# 03_BGT24LTR11.net
KiCad netlist of a schematic drawn in Altium Designer
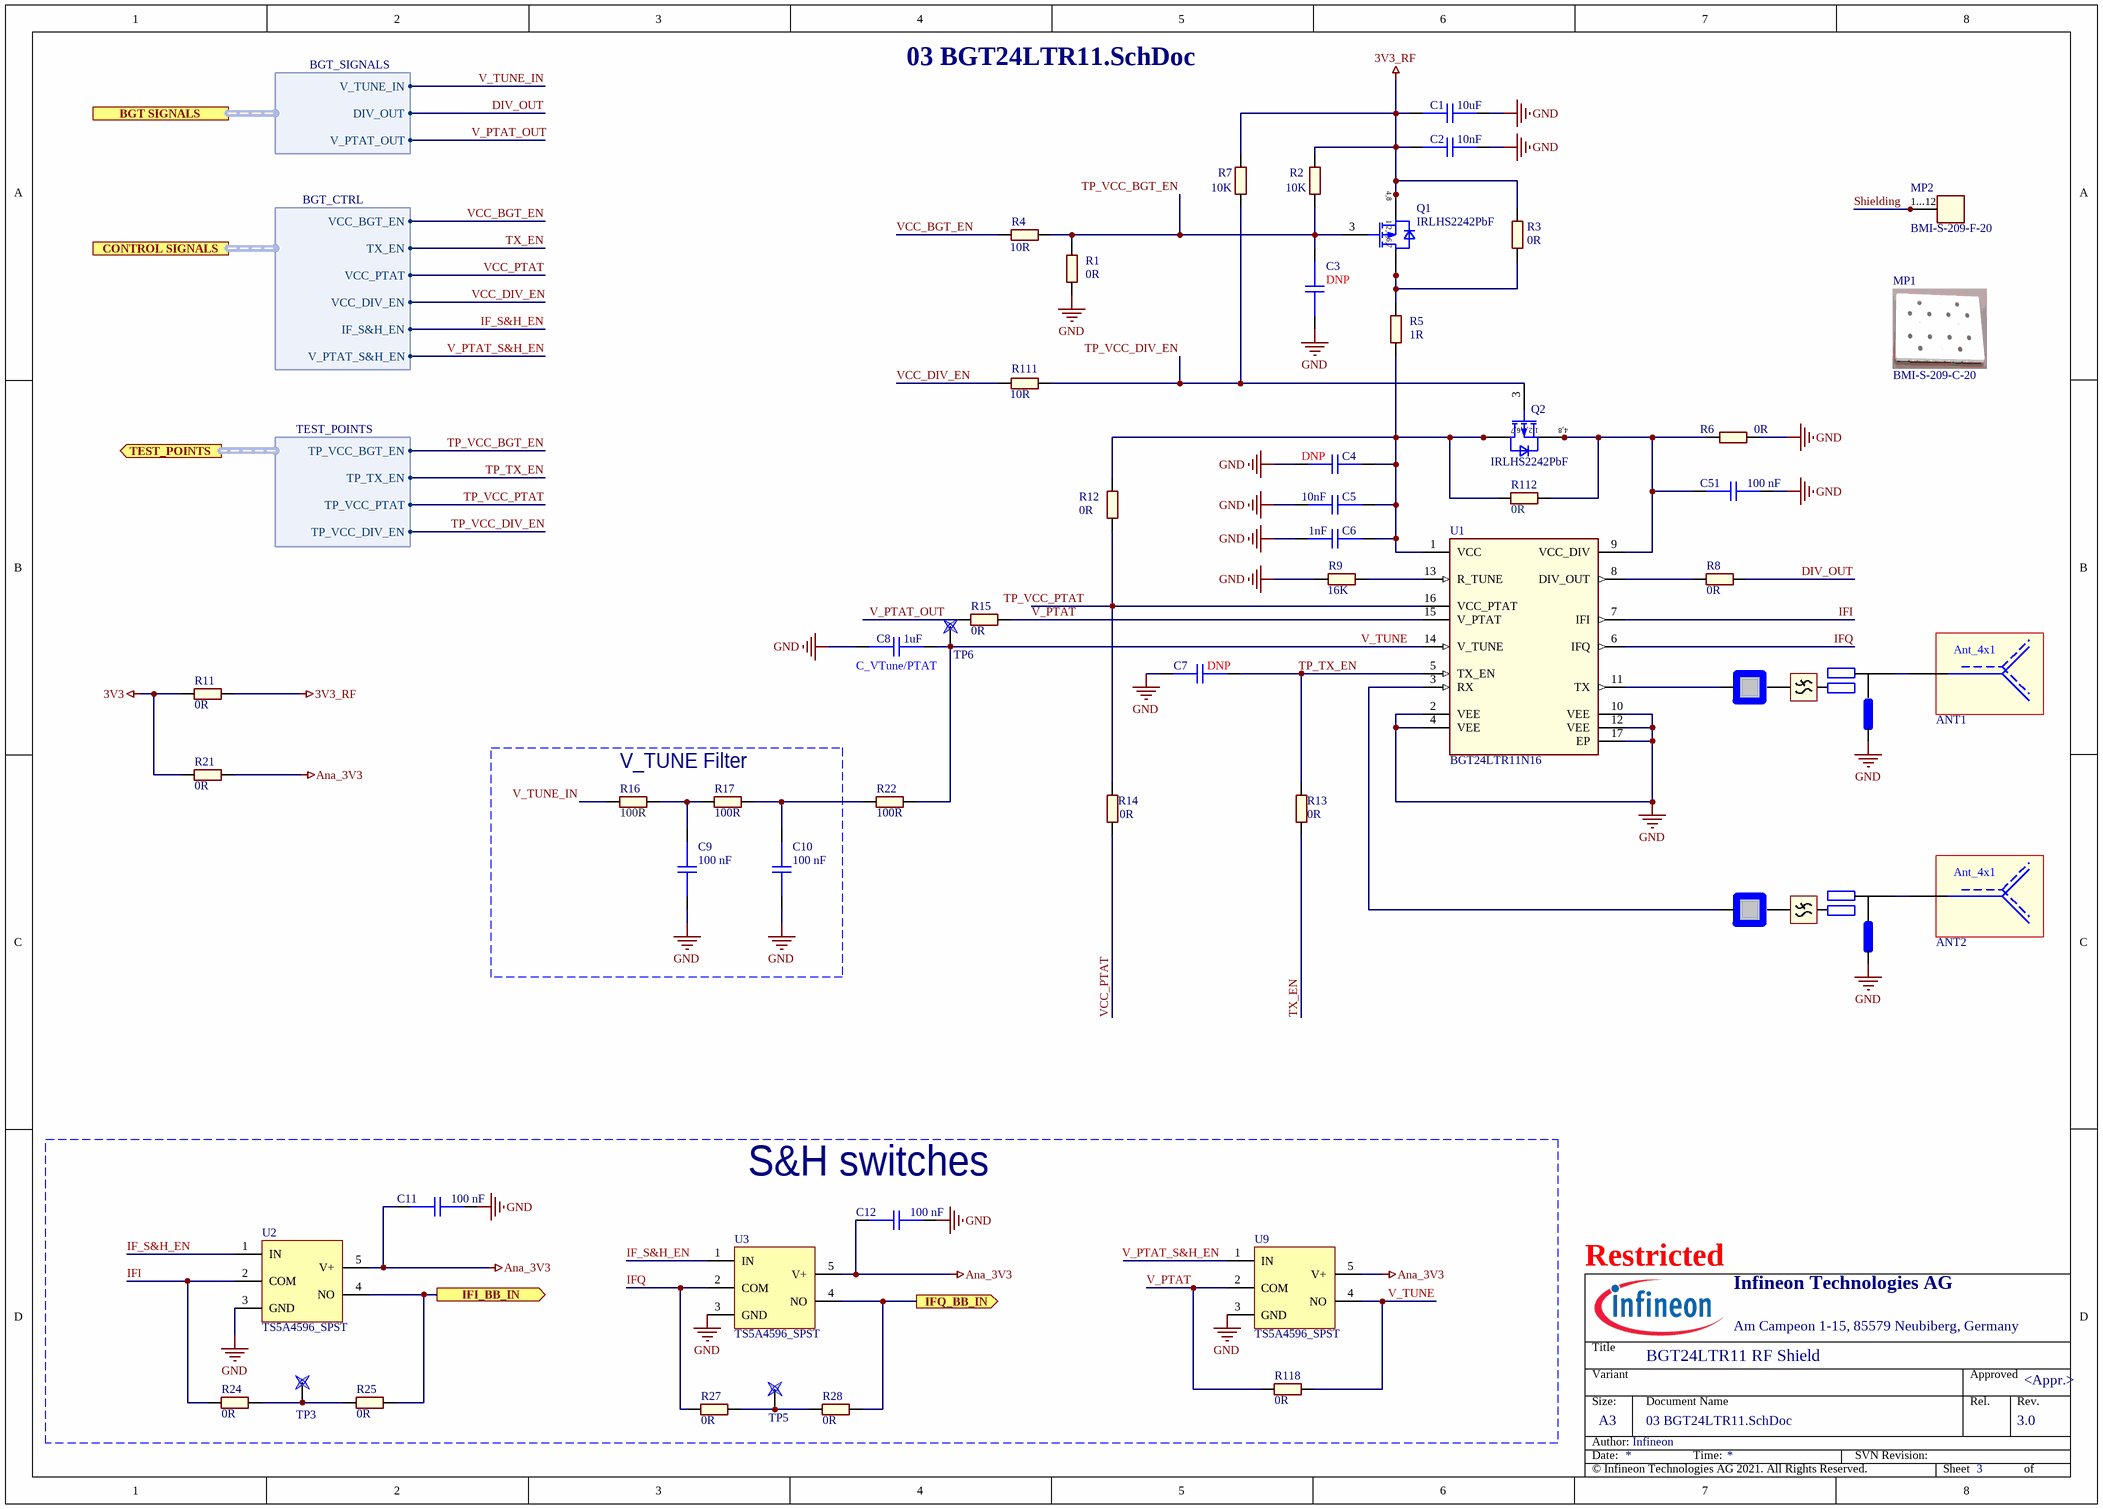
[diagram p0: 03 BGT24LTR11.SchDoc]

(export (version "E")
  (design (tool "Eeschema 10.0.6"))
  (components
    (comp (ref "ANT1")
      (value "24GHZ S2G Antenna 4X1 Patch Array")
      (footprint "BGT24LTR11_RF-Shield_Board_V3.0:S2G_ANT")
      (libsource (lib "BGT24LTR11 RF-Shield Board V0_5") (part "24GHz_S2G_ANT"))
    )
    (comp (ref "ANT2")
      (value "24GHZ S2G Antenna 4X1 Patch Array")
      (footprint "BGT24LTR11_RF-Shield_Board_V3.0:S2G_ANT")
      (libsource (lib "BGT24LTR11 RF-Shield Board V0_5") (part "24GHz_S2G_ANT"))
    )
    (comp (ref "C1")
      (value "10uF")
      (footprint "CAPC1005X55N-0_2")
      (description "General Purpose Surface Mount Ceramic Capacitor")
      (fields (field (name "PARTNUMBER") "CAP01010597") (field (name "VOLTAGE") "10Vdc"))
      (libsource (lib "DB_External_Capacitor") (part "c_std_a"))
    )
    (comp (ref "C2")
      (value "10nF")
      (footprint "CAPC1005X55N-0_2")
      (description "General Purpose Surface Mount Ceramic Capacitor")
      (fields (field (name "PARTNUMBER") "CAP01010597") (field (name "VOLTAGE") "50Vdc"))
      (libsource (lib "DB_External_Capacitor") (part "c_std_a"))
    )
    (comp (ref "C3")
      (value "DNP")
      (footprint "CAPC1005X55N-0_2")
      (description "General Purpose Surface Mount Ceramic Capacitor")
      (fields (field (name "PARTNUMBER") "CAP01010597") (field (name "VOLTAGE") "50Vdc"))
      (libsource (lib "DB_External_Capacitor") (part "c_std_a"))
    )
    (comp (ref "C4")
      (value "DNP")
      (footprint "CAPC1005X55N-0_2")
      (description "General Purpose Surface Mount Ceramic Capacitor")
      (fields (field (name "PARTNUMBER") "CAP01010597") (field (name "VOLTAGE") "50Vdc"))
      (libsource (lib "DB_External_Capacitor") (part "c_std_a"))
    )
    (comp (ref "C5")
      (value "10nF")
      (footprint "CAPC1005X55N-0_2")
      (description "General Purpose Surface Mount Ceramic Capacitor")
      (fields (field (name "PARTNUMBER") "CAP01010597") (field (name "VOLTAGE") "50Vdc"))
      (libsource (lib "DB_External_Capacitor") (part "c_std_a"))
    )
    (comp (ref "C6")
      (value "1nF")
      (footprint "CAPC1005X55N-0_2")
      (description "General Purpose Surface Mount Ceramic Capacitor")
      (fields (field (name "PARTNUMBER") "CAP01010597") (field (name "VOLTAGE") "50Vdc"))
      (libsource (lib "DB_External_Capacitor") (part "c_std_a"))
    )
    (comp (ref "C7")
      (value "DNP")
      (footprint "CAPC1005X55N-0_2")
      (description "General Purpose Surface Mount Ceramic Capacitor")
      (fields (field (name "PARTNUMBER") "CAP01010597") (field (name "VOLTAGE") "50Vdc"))
      (libsource (lib "DB_External_Capacitor") (part "c_std_a"))
    )
    (comp (ref "C8")
      (value "1uF")
      (footprint "CAPC1005X55N-0_2")
      (description "General Purpose Surface Mount Ceramic Capacitor")
      (fields (field (name "PARTNUMBER") "CAP01010597") (field (name "VOLTAGE") "50Vdc"))
      (libsource (lib "DB_External_Capacitor") (part "c_std_a"))
    )
    (comp (ref "C9")
      (value "100 nF")
      (footprint "CAPC1005X55N-0_2")
      (description "General Purpose Surface Mount Ceramic Capacitor")
      (fields (field (name "PARTNUMBER") "CAP01010597") (field (name "VOLTAGE") "16Vdc"))
      (libsource (lib "DB_External_Capacitor") (part "c_std_a"))
    )
    (comp (ref "C10")
      (value "100 nF")
      (footprint "CAPC1005X55N-0_2")
      (description "General Purpose Surface Mount Ceramic Capacitor")
      (fields (field (name "PARTNUMBER") "CAP01010597") (field (name "VOLTAGE") "16Vdc"))
      (libsource (lib "DB_External_Capacitor") (part "c_std_a"))
    )
    (comp (ref "C11")
      (value "100 nF")
      (footprint "CAPC1005X55N-0_2")
      (description "General Purpose Surface Mount Ceramic Capacitor")
      (fields (field (name "PARTNUMBER") "CAP01010597") (field (name "VOLTAGE") "16Vdc"))
      (libsource (lib "DB_External_Capacitor") (part "c_std_a"))
    )
    (comp (ref "C12")
      (value "100 nF")
      (footprint "CAPC1005X55N-0_2")
      (description "General Purpose Surface Mount Ceramic Capacitor")
      (fields (field (name "PARTNUMBER") "CAP01010597") (field (name "VOLTAGE") "16Vdc"))
      (libsource (lib "DB_External_Capacitor") (part "c_std_a"))
    )
    (comp (ref "C51")
      (value "100 nF")
      (footprint "CAPC1005X55N-0_2")
      (description "General Purpose Surface Mount Ceramic Capacitor")
      (fields (field (name "PARTNUMBER") "CAP01010597") (field (name "VOLTAGE") "16Vdc"))
      (libsource (lib "DB_External_Capacitor") (part "c_std_a"))
    )
    (comp (ref "M1")
      (value "Maching 2nd Filter DCBlock")
      (footprint "MACHINING_LTR11")
      (libsource (lib "Matching") (part "Matching_24_Duty"))
    )
    (comp (ref "M2")
      (value "Maching 2nd Filter DCBlock")
      (footprint "OLD_MATCHING")
      (libsource (lib "Matching") (part "Matching_24_Duty"))
    )
    (comp (ref "MP1")
      (value "BMI-S-209-C-20")
      (footprint "SHIELD-BMI-S-209-C")
      (description "Standard Board Level Shield Frame Cover 1008/1010 PRE-PLATED COLD ROLLED STEEL")
      (fields (field (name "MANUFACTURER") "Laird"))
      (libsource (lib "PCBLibraryData") (part "BMI-S-209-C"))
    )
    (comp (ref "MP2")
      (value "BMI-S-209-F-20")
      (footprint "SHIELD-SMD-BMI-S-209-F")
      (description "Standard Board Level Shield Frame 1008/1010 PRE-PLATED COLD ROLLED STEEL")
      (fields (field (name "MANUFACTURER") "Laird"))
      (libsource (lib "PCBLibraryData") (part "Shield 1 12p"))
    )
    (comp (ref "Q1")
      (value "IRLHS2242PbF")
      (footprint "IRLHS2242-V")
      (description "HEXFET Power Mosfet, VDS -20V")
      (fields (field (name "PARTNUMBER") "IFX01401479") (field (name "MANUFACTURER") "Infineon Technologies"))
      (libsource (lib "DB_IFX_Components") (part "igfet_p_ch_enh_dio_1d2d3g4s5d6d7d8s_8p"))
    )
    (comp (ref "Q2")
      (value "IRLHS2242PbF")
      (footprint "IRLHS2242-V")
      (description "HEXFET Power Mosfet, VDS -20V")
      (fields (field (name "PARTNUMBER") "IFX01401479") (field (name "MANUFACTURER") "Infineon Technologies"))
      (libsource (lib "DB_IFX_Components") (part "igfet_p_ch_enh_dio_1d2d3g4s5d6d7d8s_8p"))
    )
    (comp (ref "R1")
      (value "0R")
      (footprint "RESC1005X40N_2")
      (description "0R/50V/20mOhm")
      (fields (field (name "PARTNUMBER") "RES01800000") (field (name "POWER") "1.5A"))
      (libsource (lib "DB_External_Resistor") (part "r_std_a"))
    )
    (comp (ref "R2")
      (value "10K")
      (footprint "RESC1005X40N_2")
      (description "10K/50V/20mOhm")
      (fields (field (name "PARTNUMBER") "RES01800000") (field (name "POWER") "1.5A"))
      (libsource (lib "DB_External_Resistor") (part "r_std_a"))
    )
    (comp (ref "R3")
      (value "0R")
      (footprint "RESC1005X40N_2")
      (description "0R/50V/20mOhm")
      (fields (field (name "PARTNUMBER") "RES01800000") (field (name "POWER") "1.5A"))
      (libsource (lib "DB_External_Resistor") (part "r_std_a"))
    )
    (comp (ref "R4")
      (value "10R")
      (footprint "RESC1005X40N_2")
      (description "10R/50V/20mOhm")
      (fields (field (name "PARTNUMBER") "RES01800000") (field (name "POWER") "1.5A"))
      (libsource (lib "") (part "r_std_a_1"))
    )
    (comp (ref "R5")
      (value "1R")
      (footprint "RESC1005X40N_2")
      (description "1R/50V/20mOhm")
      (fields (field (name "PARTNUMBER") "RES01800000") (field (name "POWER") "1.5A"))
      (libsource (lib "DB_External_Resistor") (part "r_std_a"))
    )
    (comp (ref "R6")
      (value "0R")
      (footprint "RESC1005X40N_2")
      (description "0R/50V/20mOhm")
      (fields (field (name "PARTNUMBER") "RES01800000") (field (name "POWER") "1.5A"))
      (libsource (lib "") (part "r_std_a_3"))
    )
    (comp (ref "R7")
      (value "10K")
      (footprint "RESC1005X40N_2")
      (description "10K/50V/20mOhm")
      (fields (field (name "PARTNUMBER") "RES01800000") (field (name "POWER") "1.5A"))
      (libsource (lib "DB_External_Resistor") (part "r_std_a"))
    )
    (comp (ref "R8")
      (value "0R")
      (footprint "RESC1005X40N_2")
      (description "0R/50V/20mOhm")
      (fields (field (name "PARTNUMBER") "RES01800000") (field (name "POWER") "1.5A"))
      (libsource (lib "") (part "r_std_a_3"))
    )
    (comp (ref "R9")
      (value "16K")
      (footprint "RESC1005X40N_2")
      (description "16K/50V/20mOhm")
      (fields (field (name "PARTNUMBER") "RES01800000") (field (name "POWER") "1.5A"))
      (libsource (lib "") (part "r_std_a_1"))
    )
    (comp (ref "R11")
      (value "0R")
      (footprint "RESC1005X40N_2")
      (description "0R/50V/20mOhm")
      (fields (field (name "PARTNUMBER") "RES01800000") (field (name "POWER") "1.5A"))
      (libsource (lib "") (part "r_std_a_1"))
    )
    (comp (ref "R12")
      (value "0R")
      (footprint "RESC1005X40N_2")
      (description "0R/50V/20mOhm")
      (fields (field (name "PARTNUMBER") "RES01800000") (field (name "POWER") "1.5A"))
      (libsource (lib "") (part "r_std_a_2"))
    )
    (comp (ref "R13")
      (value "0R")
      (footprint "RESC1005X40N_2")
      (description "0R/50V/20mOhm")
      (fields (field (name "PARTNUMBER") "RES01800000") (field (name "POWER") "1.5A"))
      (libsource (lib "DB_External_Resistor") (part "r_std_a"))
    )
    (comp (ref "R14")
      (value "0R")
      (footprint "RESC1005X40N_2")
      (description "0R/50V/20mOhm")
      (fields (field (name "PARTNUMBER") "RES01800000") (field (name "POWER") "1.5A"))
      (libsource (lib "") (part "r_std_a_2"))
    )
    (comp (ref "R15")
      (value "0R")
      (footprint "RESC1005X40N_2")
      (description "0R/50V/20mOhm")
      (fields (field (name "PARTNUMBER") "RES01800000") (field (name "POWER") "1.5A"))
      (libsource (lib "") (part "r_std_a_1"))
    )
    (comp (ref "R16")
      (value "100R")
      (footprint "RESC1005X40N_2")
      (description "100R/50V/0402")
      (fields (field (name "PARTNUMBER") "RES01800000") (field (name "POWER") "1.5A"))
      (libsource (lib "") (part "r_std_a_3"))
    )
    (comp (ref "R17")
      (value "100R")
      (footprint "RESC1005X40N_2")
      (description "100R/50V/0402")
      (fields (field (name "PARTNUMBER") "RES01800000") (field (name "POWER") "1.5A"))
      (libsource (lib "") (part "r_std_a_3"))
    )
    (comp (ref "R21")
      (value "0R")
      (footprint "RESC1005X40N_2")
      (description "0R/50V/20mOhm")
      (fields (field (name "PARTNUMBER") "RES01800000") (field (name "POWER") "1.5A"))
      (libsource (lib "") (part "r_std_a_2"))
    )
    (comp (ref "R22")
      (value "100R")
      (footprint "RESC1005X40N_2")
      (description "100R/50V/0402")
      (fields (field (name "PARTNUMBER") "RES01800000") (field (name "POWER") "1.5A"))
      (libsource (lib "") (part "r_std_a_3"))
    )
    (comp (ref "R24")
      (value "0R")
      (footprint "RESC1005X40N_2")
      (description "0R/50V/20mOhm")
      (fields (field (name "PARTNUMBER") "RES01800000") (field (name "POWER") "1.5A"))
      (libsource (lib "") (part "r_std_a_3"))
    )
    (comp (ref "R25")
      (value "0R")
      (footprint "RESC1005X40N_2")
      (description "0R/50V/20mOhm")
      (fields (field (name "PARTNUMBER") "RES01800000") (field (name "POWER") "1.5A"))
      (libsource (lib "") (part "r_std_a_3"))
    )
    (comp (ref "R27")
      (value "0R")
      (footprint "RESC1005X40N_2")
      (description "0R/50V/20mOhm")
      (fields (field (name "PARTNUMBER") "RES01800000") (field (name "POWER") "1.5A"))
      (libsource (lib "") (part "r_std_a_3"))
    )
    (comp (ref "R28")
      (value "0R")
      (footprint "RESC1005X40N_2")
      (description "0R/50V/20mOhm")
      (fields (field (name "PARTNUMBER") "RES01800000") (field (name "POWER") "1.5A"))
      (libsource (lib "") (part "r_std_a_3"))
    )
    (comp (ref "R111")
      (value "10R")
      (footprint "RESC1005X40N_2")
      (description "10R/50V/20mOhm")
      (fields (field (name "PARTNUMBER") "RES01800000") (field (name "POWER") "1.5A"))
      (libsource (lib "") (part "r_std_a_1"))
    )
    (comp (ref "R112")
      (value "0R")
      (footprint "RESC1005X40N_2")
      (description "0R/50V/20mOhm")
      (fields (field (name "PARTNUMBER") "RES01800000") (field (name "POWER") "1.5A"))
      (libsource (lib "") (part "r_std_a_3"))
    )
    (comp (ref "R118")
      (value "0R")
      (footprint "RESC1005X40N_2")
      (description "0R/50V/20mOhm")
      (fields (field (name "PARTNUMBER") "RES01800000") (field (name "POWER") "1.5A"))
      (libsource (lib "") (part "r_std_a_3"))
    )
    (comp (ref "TP3")
      (value "Testpoint")
      (footprint "TP1.5MM")
      (libsource (lib "altium-import") (part "root_0_P_PRUEFPAD_"))
    )
    (comp (ref "TP5")
      (value "Testpoint")
      (footprint "TP1.5MM")
      (libsource (lib "altium-import") (part "root_0_P_PRUEFPAD_"))
    )
    (comp (ref "TP6")
      (value "Testpoint")
      (footprint "TP1.5MM")
      (libsource (lib "altium-import") (part "root_0_P_PRUEFPAD_"))
    )
    (comp (ref "U1")
      (value "BGT24LTR11N16")
      (footprint "PQFN50P240X240X77-17N-V")
      (description "Silicon Germanium 24GHz Radar Transceiver MMIC")
      (fields (field (name "PARTNUMBER") "IFX01401046") (field (name "MANUFACTURER") "Infineon Technologies"))
      (libsource (lib "DB_IFX_Components") (part "BGT24LTR11N16"))
    )
    (comp (ref "U2")
      (value "TS5A4596_SPST")
      (footprint "TS5A4597")
      (description "Single-Channel 8ohm SPST Analog Switch TS5A4596_SPST")
      (libsource (lib "Component") (part "TS5A4596DCKRSC70"))
    )
    (comp (ref "U3")
      (value "TS5A4596_SPST")
      (footprint "TS5A4597")
      (libsource (lib "Component") (part "TS5A4596DCKRSC70"))
    )
    (comp (ref "U9")
      (value "TS5A4596_SPST")
      (footprint "TS5A4597")
      (libsource (lib "Component") (part "TS5A4596DCKRSC70"))
    )
  )
  (nets
    (net (code "4") (name "/DIV_OUT") (class "Default")
      (node (ref "R8") (pin "1") (pinfunction "1_1") (pintype "passive"))
    )
    (net (code "5") (name "/IFI") (class "Default")
      (node (ref "R24") (pin "2") (pinfunction "2_2") (pintype "passive"))
      (node (ref "U1") (pin "7") (pinfunction "IFI_7") (pintype "output"))
      (node (ref "U2") (pin "2") (pinfunction "COM_2") (pintype "passive"))
    )
    (net (code "6") (name "/IFI_BB_IN") (class "Default")
      (node (ref "R25") (pin "1") (pinfunction "1_1") (pintype "passive"))
      (node (ref "U2") (pin "4") (pinfunction "NO_4") (pintype "passive"))
    )
    (net (code "7") (name "/IFQ") (class "Default")
      (node (ref "R27") (pin "2") (pinfunction "2_2") (pintype "passive"))
      (node (ref "U1") (pin "6") (pinfunction "IFQ_6") (pintype "output"))
      (node (ref "U3") (pin "2") (pinfunction "COM_2") (pintype "passive"))
    )
    (net (code "8") (name "/IFQ_BB_IN") (class "Default")
      (node (ref "R28") (pin "1") (pinfunction "1_1") (pintype "passive"))
      (node (ref "U3") (pin "4") (pinfunction "NO_4") (pintype "passive"))
    )
    (net (code "9") (name "/IF_S&H_EN") (class "Default")
      (node (ref "U2") (pin "1") (pinfunction "IN_1") (pintype "passive"))
      (node (ref "U3") (pin "1") (pinfunction "IN_1") (pintype "passive"))
    )
    (net (code "10") (name "/Shielding") (class "Default")
      (node (ref "MP2") (pin "1") (pinfunction "1_1") (pintype "passive"))
      (node (ref "MP2") (pin "2") (pinfunction "2_2") (pintype "passive"))
      (node (ref "MP2") (pin "3") (pinfunction "3_3") (pintype "passive"))
      (node (ref "MP2") (pin "4") (pinfunction "4_4") (pintype "passive"))
    )
    (net (code "11") (name "/TP_TX_EN") (class "Default")
      (node (ref "C7") (pin "1") (pinfunction "1_1") (pintype "passive"))
      (node (ref "R13") (pin "2") (pinfunction "2_2") (pintype "passive"))
      (node (ref "U1") (pin "5") (pinfunction "TX_EN_5") (pintype "input"))
    )
    (net (code "12") (name "/TP_VCC_BGT_EN") (class "Default")
      (node (ref "C3") (pin "2") (pinfunction "2_2") (pintype "passive"))
      (node (ref "Q1") (pin "3") (pinfunction "GATE_3") (pintype "passive"))
      (node (ref "R1") (pin "2") (pinfunction "2_2") (pintype "passive"))
      (node (ref "R2") (pin "1") (pinfunction "1_1") (pintype "passive"))
      (node (ref "R4") (pin "2") (pinfunction "2_2") (pintype "passive"))
    )
    (net (code "13") (name "/TP_VCC_DIV_EN") (class "Default")
      (node (ref "Q2") (pin "3") (pinfunction "GATE_3") (pintype "passive"))
      (node (ref "R111") (pin "2") (pinfunction "2_2") (pintype "passive"))
      (node (ref "R7") (pin "1") (pinfunction "1_1") (pintype "passive"))
    )
    (net (code "14") (name "/TP_VCC_PTAT") (class "Default")
      (node (ref "R12") (pin "2") (pinfunction "2_2") (pintype "passive"))
      (node (ref "R14") (pin "1") (pinfunction "1_1") (pintype "passive"))
      (node (ref "U1") (pin "16") (pinfunction "VCC_PTAT_16") (pintype "power_in"))
    )
    (net (code "15") (name "/TX_EN") (class "Default")
      (node (ref "R13") (pin "1") (pinfunction "1_1") (pintype "passive"))
    )
    (net (code "16") (name "/VCC_BGT_EN") (class "Default")
      (node (ref "R4") (pin "1") (pinfunction "1_1") (pintype "passive"))
    )
    (net (code "17") (name "/VCC_DIV_EN") (class "Default")
      (node (ref "R111") (pin "1") (pinfunction "1_1") (pintype "passive"))
    )
    (net (code "18") (name "/VCC_PTAT") (class "Default")
      (node (ref "R14") (pin "2") (pinfunction "2_2") (pintype "passive"))
    )
    (net (code "19") (name "/V_PTAT") (class "Default")
      (node (ref "R118") (pin "2") (pinfunction "2_2") (pintype "passive"))
      (node (ref "R15") (pin "2") (pinfunction "2_2") (pintype "passive"))
      (node (ref "U1") (pin "15") (pinfunction "V_PTAT_15") (pintype "power_in"))
      (node (ref "U9") (pin "2") (pinfunction "COM_2") (pintype "passive"))
    )
    (net (code "20") (name "/V_PTAT_OUT") (class "Default")
      (node (ref "R15") (pin "1") (pinfunction "1_1") (pintype "passive"))
    )
    (net (code "21") (name "/V_PTAT_S&H_EN") (class "Default")
      (node (ref "U9") (pin "1") (pinfunction "IN_1") (pintype "passive"))
    )
    (net (code "22") (name "/V_TUNE") (class "Default")
      (node (ref "C8") (pin "1") (pinfunction "1_1") (pintype "passive"))
      (node (ref "R118") (pin "1") (pinfunction "1_1") (pintype "passive"))
      (node (ref "R22") (pin "1") (pinfunction "1_1") (pintype "passive"))
      (node (ref "TP6") (pin "1") (pinfunction "1_1") (pintype "passive"))
      (node (ref "U1") (pin "14") (pinfunction "V_TUNE_14") (pintype "input"))
      (node (ref "U9") (pin "4") (pinfunction "NO_4") (pintype "passive"))
    )
    (net (code "23") (name "/V_TUNE_IN") (class "Default")
      (node (ref "R16") (pin "2") (pinfunction "2_2") (pintype "passive"))
    )
    (net (code "27") (name "3V3") (class "Default")
      (node (ref "R11") (pin "1") (pinfunction "1_1") (pintype "passive"))
      (node (ref "R21") (pin "2") (pinfunction "2_2") (pintype "passive"))
    )
    (net (code "28") (name "3V3_RF") (class "Default")
      (node (ref "C1") (pin "1") (pinfunction "1_1") (pintype "passive"))
      (node (ref "C2") (pin "1") (pinfunction "1_1") (pintype "passive"))
      (node (ref "Q1") (pin "4") (pinfunction "SOURCE1_4") (pintype "passive"))
      (node (ref "Q1") (pin "8") (pinfunction "SOURCE2_8") (pintype "passive"))
      (node (ref "R11") (pin "2") (pinfunction "2_2") (pintype "passive"))
      (node (ref "R2") (pin "2") (pinfunction "2_2") (pintype "passive"))
      (node (ref "R3") (pin "2") (pinfunction "2_2") (pintype "passive"))
      (node (ref "R7") (pin "2") (pinfunction "2_2") (pintype "passive"))
    )
    (net (code "29") (name "Ana_3V3") (class "Default")
      (node (ref "C11") (pin "2") (pinfunction "2_2") (pintype "passive"))
      (node (ref "C12") (pin "2") (pinfunction "2_2") (pintype "passive"))
      (node (ref "R21") (pin "1") (pinfunction "1_1") (pintype "passive"))
      (node (ref "U2") (pin "5") (pinfunction "V+_5") (pintype "passive"))
      (node (ref "U3") (pin "5") (pinfunction "V+_5") (pintype "passive"))
      (node (ref "U9") (pin "5") (pinfunction "V+_5") (pintype "passive"))
    )
    (net (code "30") (name "GND") (class "Default")
      (node (ref "C1") (pin "2") (pinfunction "2_2") (pintype "passive"))
      (node (ref "C10") (pin "1") (pinfunction "1_1") (pintype "passive"))
      (node (ref "C11") (pin "1") (pinfunction "1_1") (pintype "passive"))
      (node (ref "C12") (pin "1") (pinfunction "1_1") (pintype "passive"))
      (node (ref "C2") (pin "2") (pinfunction "2_2") (pintype "passive"))
      (node (ref "C3") (pin "1") (pinfunction "1_1") (pintype "passive"))
      (node (ref "C4") (pin "1") (pinfunction "1_1") (pintype "passive"))
      (node (ref "C5") (pin "1") (pinfunction "1_1") (pintype "passive"))
      (node (ref "C51") (pin "1") (pinfunction "1_1") (pintype "passive"))
      (node (ref "C6") (pin "1") (pinfunction "1_1") (pintype "passive"))
      (node (ref "C7") (pin "2") (pinfunction "2_2") (pintype "passive"))
      (node (ref "C8") (pin "2") (pinfunction "2_2") (pintype "passive"))
      (node (ref "C9") (pin "1") (pinfunction "1_1") (pintype "passive"))
      (node (ref "M1") (pin "3") (pinfunction "GND_3") (pintype "passive"))
      (node (ref "M2") (pin "3") (pinfunction "GND_3") (pintype "passive"))
      (node (ref "R1") (pin "1") (pinfunction "1_1") (pintype "passive"))
      (node (ref "R6") (pin "1") (pinfunction "1_1") (pintype "passive"))
      (node (ref "R9") (pin "1") (pinfunction "1_1") (pintype "passive"))
      (node (ref "U1") (pin "10") (pinfunction "VEE_10") (pintype "power_in"))
      (node (ref "U1") (pin "12") (pinfunction "VEE_12") (pintype "power_in"))
      (node (ref "U1") (pin "17") (pinfunction "EP_17") (pintype "power_in"))
      (node (ref "U1") (pin "2") (pinfunction "VEE_2") (pintype "power_in"))
      (node (ref "U1") (pin "4") (pinfunction "VEE_4") (pintype "power_in"))
      (node (ref "U2") (pin "3") (pinfunction "GND_3") (pintype "passive"))
      (node (ref "U3") (pin "3") (pinfunction "GND_3") (pintype "passive"))
      (node (ref "U9") (pin "3") (pinfunction "GND_3") (pintype "passive"))
    )
    (net (code "31") (name "Net-(C9-Pad2)") (class "Default")
      (node (ref "C9") (pin "2") (pinfunction "2_2") (pintype "passive"))
      (node (ref "R16") (pin "1") (pinfunction "1_1") (pintype "passive"))
      (node (ref "R17") (pin "2") (pinfunction "2_2") (pintype "passive"))
    )
    (net (code "32") (name "Net-(C10-Pad2)") (class "Default")
      (node (ref "C10") (pin "2") (pinfunction "2_2") (pintype "passive"))
      (node (ref "R17") (pin "1") (pinfunction "1_1") (pintype "passive"))
      (node (ref "R22") (pin "2") (pinfunction "2_2") (pintype "passive"))
    )
    (net (code "33") (name "Net-(M1-ANT)") (class "Default")
      (node (ref "ANT1") (pin "1") (pinfunction "1_1") (pintype "passive"))
      (node (ref "M1") (pin "2") (pinfunction "ANT_2") (pintype "passive"))
    )
    (net (code "34") (name "Net-(M1-IC_IN)") (class "Default")
      (node (ref "M1") (pin "1") (pinfunction "IC_IN_1") (pintype "passive"))
      (node (ref "U1") (pin "11") (pinfunction "TX_11") (pintype "output"))
    )
    (net (code "35") (name "Net-(M2-ANT)") (class "Default")
      (node (ref "ANT2") (pin "1") (pinfunction "1_1") (pintype "passive"))
      (node (ref "M2") (pin "2") (pinfunction "ANT_2") (pintype "passive"))
    )
    (net (code "36") (name "Net-(M2-IC_IN)") (class "Default")
      (node (ref "M2") (pin "1") (pinfunction "IC_IN_1") (pintype "passive"))
      (node (ref "U1") (pin "3") (pinfunction "RX_3") (pintype "input"))
    )
    (net (code "37") (name "Net-(Q1-DRAIN1)") (class "Default")
      (node (ref "Q1") (pin "1") (pinfunction "DRAIN1_1") (pintype "passive"))
      (node (ref "Q1") (pin "2") (pinfunction "DRAIN2_2") (pintype "passive"))
      (node (ref "Q1") (pin "5") (pinfunction "DRAIN3_5") (pintype "passive"))
      (node (ref "Q1") (pin "6") (pinfunction "DRAIN4_6") (pintype "passive"))
      (node (ref "Q1") (pin "7") (pinfunction "DRAIN5_7") (pintype "passive"))
      (node (ref "R3") (pin "1") (pinfunction "1_1") (pintype "passive"))
      (node (ref "R5") (pin "2") (pinfunction "2_2") (pintype "passive"))
    )
    (net (code "38") (name "Net-(Q2-DRAIN1)") (class "Default")
      (node (ref "C4") (pin "2") (pinfunction "2_2") (pintype "passive"))
      (node (ref "C5") (pin "2") (pinfunction "2_2") (pintype "passive"))
      (node (ref "C6") (pin "2") (pinfunction "2_2") (pintype "passive"))
      (node (ref "Q2") (pin "1") (pinfunction "DRAIN1_1") (pintype "passive"))
      (node (ref "Q2") (pin "2") (pinfunction "DRAIN2_2") (pintype "passive"))
      (node (ref "Q2") (pin "5") (pinfunction "DRAIN3_5") (pintype "passive"))
      (node (ref "Q2") (pin "6") (pinfunction "DRAIN4_6") (pintype "passive"))
      (node (ref "Q2") (pin "7") (pinfunction "DRAIN5_7") (pintype "passive"))
      (node (ref "R112") (pin "2") (pinfunction "2_2") (pintype "passive"))
      (node (ref "R12") (pin "1") (pinfunction "1_1") (pintype "passive"))
      (node (ref "R5") (pin "1") (pinfunction "1_1") (pintype "passive"))
      (node (ref "U1") (pin "1") (pinfunction "VCC_1") (pintype "power_in"))
    )
    (net (code "39") (name "Net-(Q2-SOURCE1)") (class "Default")
      (node (ref "C51") (pin "2") (pinfunction "2_2") (pintype "passive"))
      (node (ref "Q2") (pin "4") (pinfunction "SOURCE1_4") (pintype "passive"))
      (node (ref "Q2") (pin "8") (pinfunction "SOURCE2_8") (pintype "passive"))
      (node (ref "R112") (pin "1") (pinfunction "1_1") (pintype "passive"))
      (node (ref "R6") (pin "2") (pinfunction "2_2") (pintype "passive"))
      (node (ref "U1") (pin "9") (pinfunction "VCC_DIV_9") (pintype "power_in"))
    )
    (net (code "40") (name "Net-(R24-Pad1)") (class "Default")
      (node (ref "R24") (pin "1") (pinfunction "1_1") (pintype "passive"))
      (node (ref "R25") (pin "2") (pinfunction "2_2") (pintype "passive"))
      (node (ref "TP3") (pin "1") (pinfunction "1_1") (pintype "passive"))
    )
    (net (code "41") (name "Net-(R27-Pad1)") (class "Default")
      (node (ref "R27") (pin "1") (pinfunction "1_1") (pintype "passive"))
      (node (ref "R28") (pin "2") (pinfunction "2_2") (pintype "passive"))
      (node (ref "TP5") (pin "1") (pinfunction "1_1") (pintype "passive"))
    )
    (net (code "42") (name "Net-(U1-DIV_OUT)") (class "Default")
      (node (ref "R8") (pin "2") (pinfunction "2_2") (pintype "passive"))
      (node (ref "U1") (pin "8") (pinfunction "DIV_OUT_8") (pintype "output"))
    )
    (net (code "43") (name "Net-(U1-R_TUNE)") (class "Default")
      (node (ref "R9") (pin "2") (pinfunction "2_2") (pintype "passive"))
      (node (ref "U1") (pin "13") (pinfunction "R_TUNE_13") (pintype "input"))
    )
  )
)
